# TranslationDir2Chan.net
KiCad netlist of a schematic drawn in Altium Designer
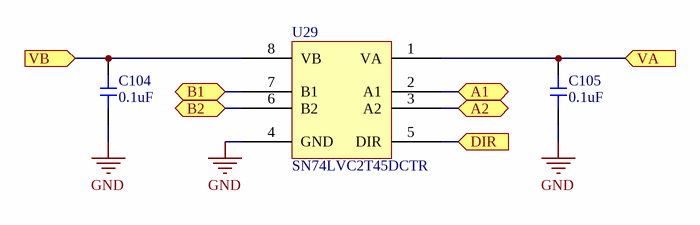
[diagram p0: TranslationDir2Chan.SchDoc]

(export (version "E")
  (design (tool "Eeschema 10.0.6"))
  (components
    (comp (ref "C104")
      (value "0.1uF")
      (footprint "0603-CAP")
      (description "Capacitor")
      (libsource (lib "AMDC") (part "Capacitor"))
    )
    (comp (ref "C105")
      (value "0.1uF")
      (footprint "0603-CAP")
      (description "Capacitor")
      (libsource (lib "AMDC") (part "Capacitor"))
    )
    (comp (ref "U29")
      (value "SN74LVC2T45DCTR")
      (footprint "TSOP65P400X130-8N")
      (description "IC BUS TRANSCVR 2BIT N-INV SM8")
      (libsource (lib "AMDC") (part "SN74LVC2T45DCTR"))
    )
  )
  (nets
    (net (code "1") (name "/A1") (class "Default")
      (node (ref "U29") (pin "2") (pinfunction "A1_2") (pintype "passive"))
    )
    (net (code "2") (name "/A2") (class "Default")
      (node (ref "U29") (pin "3") (pinfunction "A2_3") (pintype "passive"))
    )
    (net (code "3") (name "/B1") (class "Default")
      (node (ref "U29") (pin "7") (pinfunction "B1_7") (pintype "passive"))
    )
    (net (code "4") (name "/B2") (class "Default")
      (node (ref "U29") (pin "6") (pinfunction "B2_6") (pintype "passive"))
    )
    (net (code "5") (name "/DIR") (class "Default")
      (node (ref "U29") (pin "5") (pinfunction "DIR_5") (pintype "passive"))
    )
    (net (code "6") (name "/VA") (class "Default")
      (node (ref "C105") (pin "1") (pinfunction "1_1") (pintype "passive"))
      (node (ref "U29") (pin "1") (pinfunction "VA_1") (pintype "passive"))
    )
    (net (code "7") (name "/VB") (class "Default")
      (node (ref "C104") (pin "1") (pinfunction "1_1") (pintype "passive"))
      (node (ref "U29") (pin "8") (pinfunction "VB_8") (pintype "passive"))
    )
    (net (code "8") (name "GND") (class "Default")
      (node (ref "C104") (pin "2") (pinfunction "2_2") (pintype "passive"))
      (node (ref "C105") (pin "2") (pinfunction "2_2") (pintype "passive"))
      (node (ref "U29") (pin "4") (pinfunction "GND_4") (pintype "passive"))
    )
  )
)
